# Audio-Sound_Breakout-v10.net
KiCad netlist of a schematic drawn in EAGLE
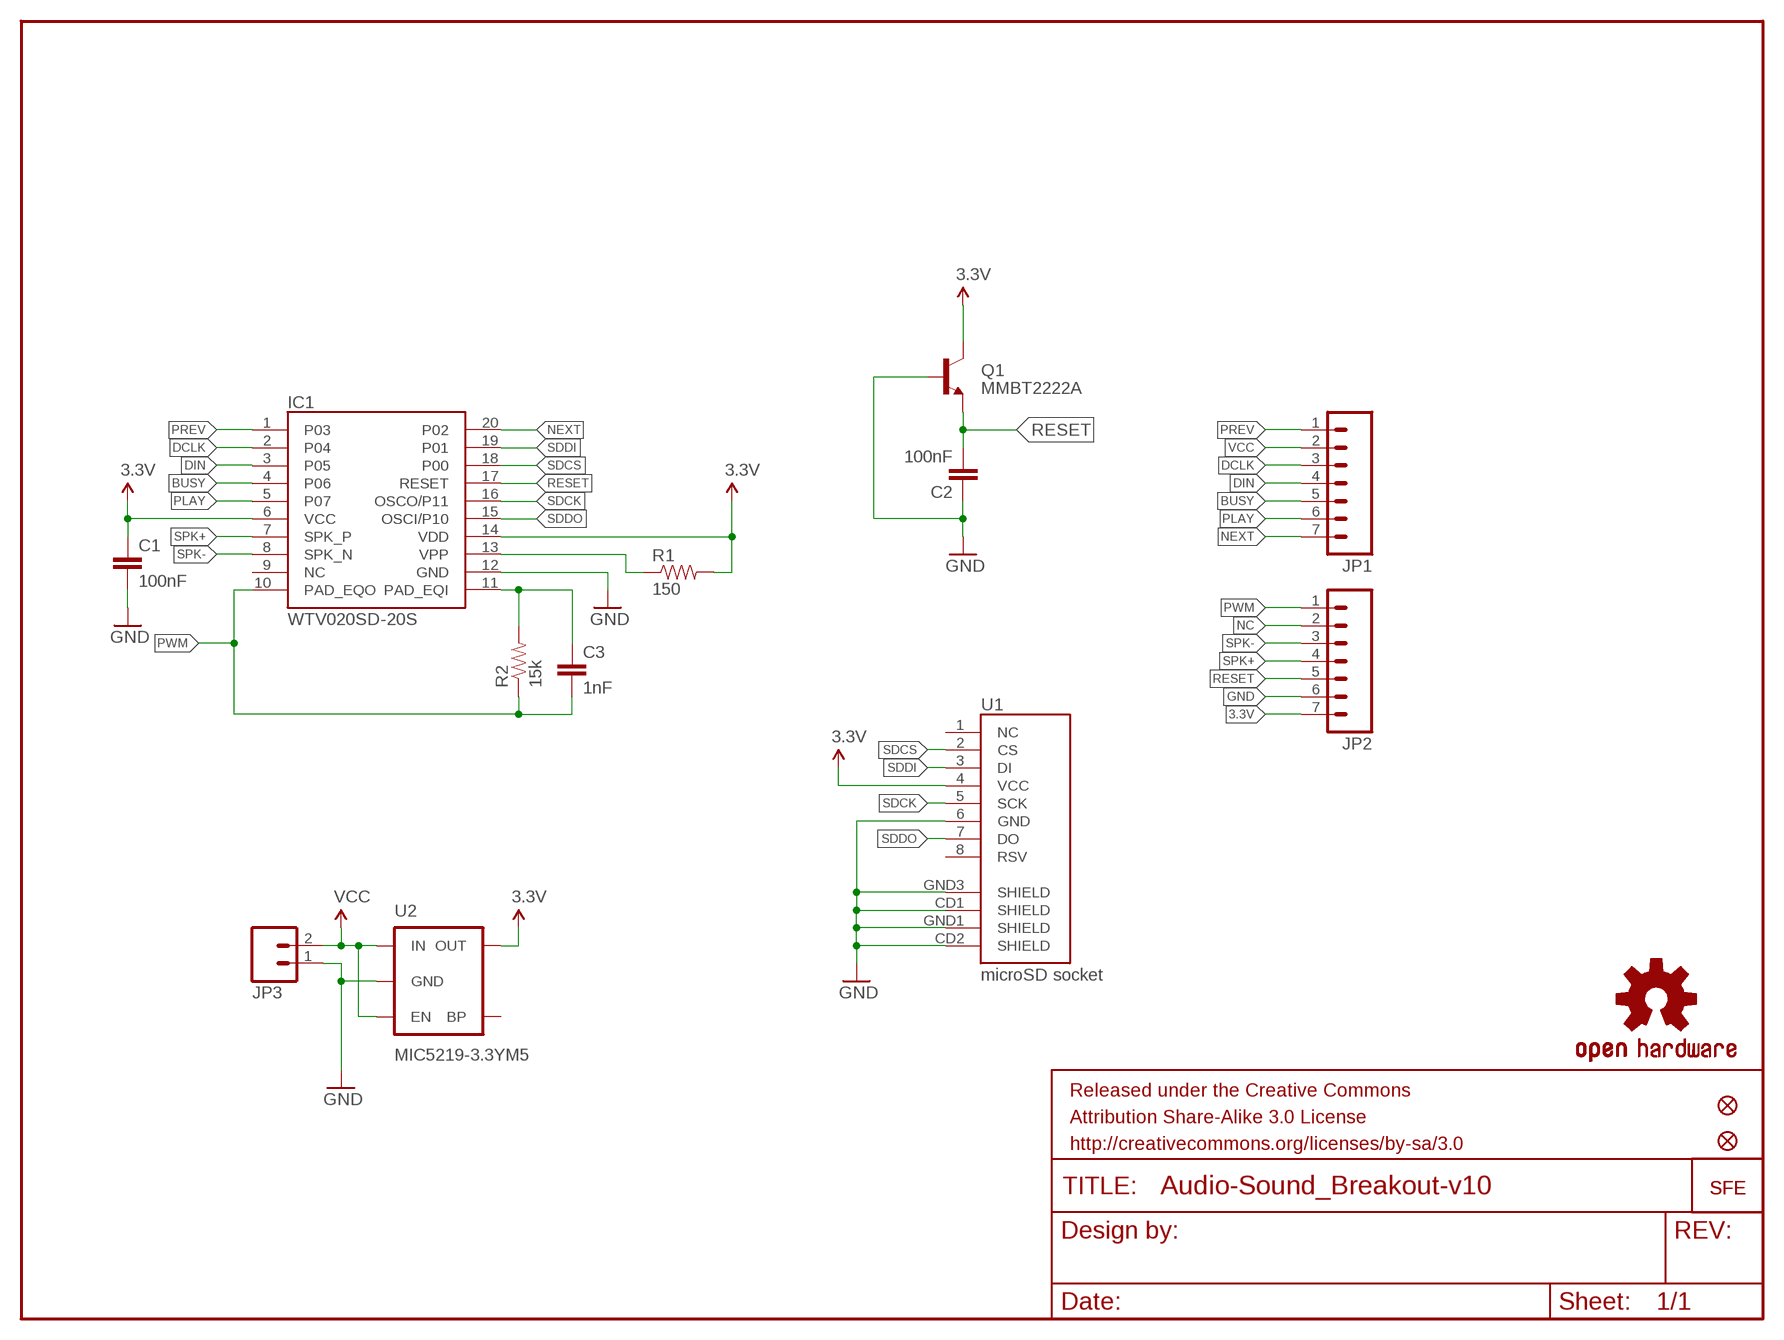
[diagram p0: schematic, sheet 1]

(export (version "E")
  (design (tool "Eeschema 10.0.6"))
  (components
    (comp (ref "C1")
      (value "100nF")
      (footprint "eagle-import:0402-CAP")
      (libsource (lib "eagle-import") (part "CAP0402-CAP"))
    )
    (comp (ref "C2")
      (value "100nF")
      (footprint "eagle-import:0402-CAP")
      (fields (field (name "MFG") "Multiple"))
      (libsource (lib "eagle-import") (part "CAP0402-CAP"))
    )
    (comp (ref "C3")
      (value "1nF")
      (footprint "eagle-import:0402-CAP")
      (libsource (lib "eagle-import") (part "CAP0402-CAP"))
    )
    (comp (ref "IC1")
      (value "WTV020SD-20S")
      (footprint "eagle-import:SSOP_20")
      (fields (field (name "SKU") "NA"))
      (libsource (lib "eagle-import") (part "WTV020SD"))
    )
    (comp (ref "JP1")
      (value "M07")
      (footprint "eagle-import:1X07")
      (libsource (lib "eagle-import") (part "M07"))
    )
    (comp (ref "JP2")
      (value "M07")
      (footprint "eagle-import:1X07")
      (libsource (lib "eagle-import") (part "M07"))
    )
    (comp (ref "JP3")
      (value "M02-JST-2MM-SMT")
      (footprint "eagle-import:JST-2-SMD")
      (libsource (lib "eagle-import") (part "M02-JST-2MM-SMT"))
    )
    (comp (ref "JP4")
      (value "LOGO-SFENW2")
      (footprint "eagle-import:SFE-NEW-WEB")
      (libsource (lib "eagle-import") (part "LOGO-SFENW2"))
    )
    (comp (ref "JP5")
      (value "LOGO-SFENEW")
      (footprint "eagle-import:SFE-NEW-WEBLOGO")
      (libsource (lib "eagle-import") (part "LOGO-SFENEW"))
    )
    (comp (ref "JP6")
      (value "FIDUCIALUFIDUCIAL")
      (footprint "eagle-import:MICRO-FIDUCIAL")
      (libsource (lib "eagle-import") (part "FIDUCIALUFIDUCIAL"))
    )
    (comp (ref "JP7")
      (value "FIDUCIALUFIDUCIAL")
      (footprint "eagle-import:MICRO-FIDUCIAL")
      (libsource (lib "eagle-import") (part "FIDUCIALUFIDUCIAL"))
    )
    (comp (ref "Q1")
      (value "MMBT2222A")
      (footprint "eagle-import:SOT23")
      (libsource (lib "eagle-import") (part "TRANSISTOR_NPNSOT23"))
    )
    (comp (ref "R1")
      (value "150")
      (footprint "eagle-import:0402-RES")
      (libsource (lib "eagle-import") (part "RESISTOR0402-RES"))
    )
    (comp (ref "R2")
      (value "15k")
      (footprint "eagle-import:0402-RES")
      (libsource (lib "eagle-import") (part "RESISTOR0402-RES"))
    )
    (comp (ref "U$1")
      (value "OSHW-LOGOS")
      (footprint "eagle-import:OSHW-LOGO-S")
      (libsource (lib "eagle-import") (part "OSHW-LOGOS"))
    )
    (comp (ref "U1")
      (value "microSD socket")
      (footprint "eagle-import:MICRO-SD-SOCKET-PP")
      (libsource (lib "eagle-import") (part "USD-SOCKETNEW"))
    )
    (comp (ref "U2")
      (value "MIC5219-3.3YM5")
      (footprint "eagle-import:SOT23-5")
      (libsource (lib "eagle-import") (part "V_REG_MIC5219SMD"))
    )
  )
  (nets
    (net (code "1") (name "3.3V") (class "Default")
      (node (ref "C1") (pin "1") (pinfunction "1_1") (pintype "passive"))
      (node (ref "IC1") (pin "14") (pinfunction "VDD_14") (pintype "bidirectional"))
      (node (ref "IC1") (pin "6") (pinfunction "VCC_6") (pintype "bidirectional"))
      (node (ref "JP2") (pin "7") (pinfunction "7_7") (pintype "passive"))
      (node (ref "Q1") (pin "3") (pinfunction "C_3") (pintype "passive"))
      (node (ref "R1") (pin "2") (pinfunction "2_2") (pintype "passive"))
      (node (ref "U1") (pin "4") (pinfunction "VCC_4") (pintype "bidirectional"))
      (node (ref "U2") (pin "5") (pinfunction "OUT_5") (pintype "passive"))
    )
    (net (code "2") (name "BUSY") (class "Default")
      (node (ref "IC1") (pin "4") (pinfunction "P06_4") (pintype "bidirectional"))
      (node (ref "JP1") (pin "5") (pinfunction "5_5") (pintype "passive"))
    )
    (net (code "3") (name "DCLK") (class "Default")
      (node (ref "IC1") (pin "2") (pinfunction "P04_2") (pintype "bidirectional"))
      (node (ref "JP1") (pin "3") (pinfunction "3_3") (pintype "passive"))
    )
    (net (code "4") (name "DIN") (class "Default")
      (node (ref "IC1") (pin "3") (pinfunction "P05_3") (pintype "bidirectional"))
      (node (ref "JP1") (pin "4") (pinfunction "4_4") (pintype "passive"))
    )
    (net (code "5") (name "GND") (class "Default")
      (node (ref "C1") (pin "2") (pinfunction "2_2") (pintype "passive"))
      (node (ref "C2") (pin "1") (pinfunction "1_1") (pintype "passive"))
      (node (ref "IC1") (pin "12") (pinfunction "GND_12") (pintype "bidirectional"))
      (node (ref "JP2") (pin "6") (pinfunction "6_6") (pintype "passive"))
      (node (ref "JP3") (pin "1") (pinfunction "2_1") (pintype "passive"))
      (node (ref "Q1") (pin "1") (pinfunction "B_1") (pintype "passive"))
      (node (ref "U1") (pin "6") (pinfunction "GND_6") (pintype "bidirectional"))
      (node (ref "U1") (pin "CD1") (pinfunction "SHIELD_CD1") (pintype "bidirectional"))
      (node (ref "U1") (pin "CD2") (pinfunction "SHIELD_CD2") (pintype "bidirectional"))
      (node (ref "U1") (pin "GND1") (pinfunction "SHIELD_GND1") (pintype "bidirectional"))
      (node (ref "U1") (pin "GND3") (pinfunction "SHIELD_GND3") (pintype "bidirectional"))
      (node (ref "U2") (pin "2") (pinfunction "GND_2") (pintype "input"))
    )
    (net (code "6") (name "NC") (class "Default")
      (node (ref "JP2") (pin "2") (pinfunction "2_2") (pintype "passive"))
    )
    (net (code "7") (name "NEXT") (class "Default")
      (node (ref "IC1") (pin "20") (pinfunction "P02_20") (pintype "bidirectional"))
      (node (ref "JP1") (pin "7") (pinfunction "7_7") (pintype "passive"))
    )
    (net (code "8") (name "Net-(IC1-PAD_EQI)") (class "Default")
      (node (ref "C3") (pin "1") (pinfunction "1_1") (pintype "passive"))
      (node (ref "IC1") (pin "11") (pinfunction "PAD_EQI_11") (pintype "bidirectional"))
      (node (ref "R2") (pin "2") (pinfunction "2_2") (pintype "passive"))
    )
    (net (code "9") (name "Net-(IC1-VPP)") (class "Default")
      (node (ref "IC1") (pin "13") (pinfunction "VPP_13") (pintype "bidirectional"))
      (node (ref "R1") (pin "1") (pinfunction "1_1") (pintype "passive"))
    )
    (net (code "10") (name "PLAY") (class "Default")
      (node (ref "IC1") (pin "5") (pinfunction "P07_5") (pintype "bidirectional"))
      (node (ref "JP1") (pin "6") (pinfunction "6_6") (pintype "passive"))
    )
    (net (code "11") (name "PREV") (class "Default")
      (node (ref "IC1") (pin "1") (pinfunction "P03_1") (pintype "bidirectional"))
      (node (ref "JP1") (pin "1") (pinfunction "1_1") (pintype "passive"))
    )
    (net (code "12") (name "PWM") (class "Default")
      (node (ref "C3") (pin "2") (pinfunction "2_2") (pintype "passive"))
      (node (ref "IC1") (pin "10") (pinfunction "PAD_EQO_10") (pintype "bidirectional"))
      (node (ref "JP2") (pin "1") (pinfunction "1_1") (pintype "passive"))
      (node (ref "R2") (pin "1") (pinfunction "1_1") (pintype "passive"))
    )
    (net (code "13") (name "RESET") (class "Default")
      (node (ref "C2") (pin "2") (pinfunction "2_2") (pintype "passive"))
      (node (ref "IC1") (pin "17") (pinfunction "RESET_17") (pintype "bidirectional"))
      (node (ref "JP2") (pin "5") (pinfunction "5_5") (pintype "passive"))
      (node (ref "Q1") (pin "2") (pinfunction "E_2") (pintype "passive"))
    )
    (net (code "14") (name "SDCK") (class "Default")
      (node (ref "IC1") (pin "16") (pinfunction "OSCO/P11_16") (pintype "bidirectional"))
      (node (ref "U1") (pin "5") (pinfunction "SCK_5") (pintype "bidirectional"))
    )
    (net (code "15") (name "SDCS") (class "Default")
      (node (ref "IC1") (pin "18") (pinfunction "P00_18") (pintype "bidirectional"))
      (node (ref "U1") (pin "2") (pinfunction "CS_2") (pintype "bidirectional"))
    )
    (net (code "16") (name "SDDI") (class "Default")
      (node (ref "IC1") (pin "19") (pinfunction "P01_19") (pintype "bidirectional"))
      (node (ref "U1") (pin "3") (pinfunction "DI_3") (pintype "bidirectional"))
    )
    (net (code "17") (name "SDDO") (class "Default")
      (node (ref "IC1") (pin "15") (pinfunction "OSCI/P10_15") (pintype "bidirectional"))
      (node (ref "U1") (pin "7") (pinfunction "DO_7") (pintype "bidirectional"))
    )
    (net (code "18") (name "SPK+") (class "Default")
      (node (ref "IC1") (pin "7") (pinfunction "SPK_P_7") (pintype "bidirectional"))
      (node (ref "JP2") (pin "4") (pinfunction "4_4") (pintype "passive"))
    )
    (net (code "19") (name "SPK-") (class "Default")
      (node (ref "IC1") (pin "8") (pinfunction "SPK_N_8") (pintype "bidirectional"))
      (node (ref "JP2") (pin "3") (pinfunction "3_3") (pintype "passive"))
    )
    (net (code "20") (name "VCC") (class "Default")
      (node (ref "JP1") (pin "2") (pinfunction "2_2") (pintype "passive"))
      (node (ref "JP3") (pin "2") (pinfunction "1_2") (pintype "passive"))
      (node (ref "U2") (pin "1") (pinfunction "IN_1") (pintype "input"))
      (node (ref "U2") (pin "3") (pinfunction "EN_3") (pintype "input"))
    )
    (net (code "21") (name "unconnected-(IC1-NC-Pad9)") (class "Default")
      (node (ref "IC1") (pin "9") (pinfunction "NC_9") (pintype "bidirectional"))
    )
    (net (code "22") (name "unconnected-(U1-NC-Pad1)") (class "Default")
      (node (ref "U1") (pin "1") (pinfunction "NC_1") (pintype "bidirectional"))
    )
    (net (code "23") (name "unconnected-(U1-RSV-Pad8)") (class "Default")
      (node (ref "U1") (pin "8") (pinfunction "RSV_8") (pintype "bidirectional"))
    )
    (net (code "24") (name "unconnected-(U2-BP-Pad4)") (class "Default")
      (node (ref "U2") (pin "4") (pinfunction "BP_4") (pintype "input"))
    )
  )
)
